# awm661tx_minimal.net
KiCad netlist of a schematic drawn in EAGLE
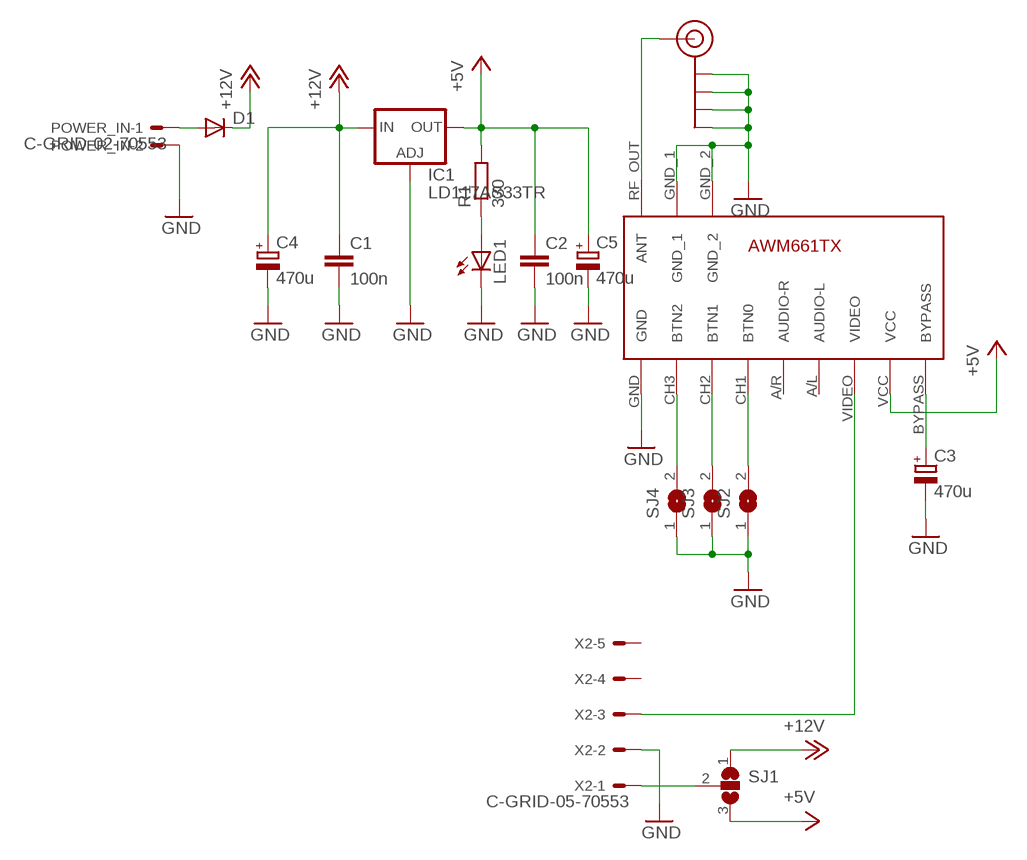
[diagram p0: schematic, sheet 1]

(export (version "E")
  (design (tool "Eeschema 10.0.6"))
  (components
    (comp (ref "C1")
      (value "100n")
      (footprint "eagle-import:C0805")
      (libsource (lib "eagle-import") (part "C-EUC0805"))
    )
    (comp (ref "C2")
      (value "100n")
      (footprint "eagle-import:C0805")
      (libsource (lib "eagle-import") (part "C-EUC0805"))
    )
    (comp (ref "C3")
      (value "470u")
      (footprint "eagle-import:150CLZ-0810")
      (libsource (lib "eagle-import") (part "CPOL-EU150CLZ-0810"))
    )
    (comp (ref "C4")
      (value "470u")
      (footprint "eagle-import:150CLZ-0810")
      (libsource (lib "eagle-import") (part "CPOL-EU150CLZ-0810"))
    )
    (comp (ref "C5")
      (value "470u")
      (footprint "eagle-import:150CLZ-0810")
      (libsource (lib "eagle-import") (part "CPOL-EU150CLZ-0810"))
    )
    (comp (ref "D1")
      (value "DIODE-MELF-MLL41")
      (footprint "eagle-import:MELF-MLL41")
      (libsource (lib "eagle-import") (part "DIODE-MELF-MLL41"))
    )
    (comp (ref "IC1")
      (value "LD117AS33TR")
      (footprint "eagle-import:SOT223")
      (libsource (lib "eagle-import") (part "LD117A?S33TR"))
    )
    (comp (ref "J$1")
      (value "SMA_EDGE")
      (footprint "eagle-import:SMA-EDGE")
      (libsource (lib "eagle-import") (part "SMA_EDGE"))
    )
    (comp (ref "LED1")
      (value "LEDCHIP-LED0805")
      (footprint "eagle-import:CHIP-LED0805")
      (libsource (lib "eagle-import") (part "LEDCHIP-LED0805"))
    )
    (comp (ref "POWER_IN")
      (value "C-GRID-02-70553")
      (footprint "eagle-import:70553-02")
      (libsource (lib "eagle-import") (part "C-GRID-02-70553"))
    )
    (comp (ref "R1")
      (value "330")
      (footprint "eagle-import:R0805")
      (libsource (lib "eagle-import") (part "R-EU_R0805"))
    )
    (comp (ref "SJ1")
      (value "SJ2W")
      (footprint "eagle-import:SJ_2")
      (libsource (lib "eagle-import") (part "SJ2W"))
    )
    (comp (ref "SJ2") (value "SJ") (footprint "eagle-import:SJ") (libsource (lib "eagle-import") (part "SJ")))
    (comp (ref "SJ3") (value "SJ") (footprint "eagle-import:SJ") (libsource (lib "eagle-import") (part "SJ")))
    (comp (ref "SJ4") (value "SJ") (footprint "eagle-import:SJ") (libsource (lib "eagle-import") (part "SJ")))
    (comp (ref "U$1")
      (value "AWM661TX")
      (footprint "eagle-import:AWM661TX")
      (libsource (lib "eagle-import") (part "AWM661TX"))
    )
    (comp (ref "X2")
      (value "C-GRID-05-70553")
      (footprint "eagle-import:70553-05")
      (libsource (lib "eagle-import") (part "C-GRID-05-70553"))
    )
  )
  (nets
    (net (code "1") (name "+5V") (class "Default")
      (node (ref "C2") (pin "1") (pinfunction "1_1") (pintype "passive"))
      (node (ref "C5") (pin "+") (pinfunction "+_+") (pintype "passive"))
      (node (ref "IC1") (pin "4") (pinfunction "OUT_4") (pintype "passive"))
      (node (ref "R1") (pin "2") (pinfunction "2_2") (pintype "passive"))
      (node (ref "SJ1") (pin "3") (pinfunction "3_3") (pintype "passive"))
      (node (ref "U$1") (pin "VCC") (pinfunction "VCC_VCC") (pintype "bidirectional"))
    )
    (net (code "2") (name "+12V") (class "Default")
      (node (ref "C1") (pin "1") (pinfunction "1_1") (pintype "passive"))
      (node (ref "C4") (pin "+") (pinfunction "+_+") (pintype "passive"))
      (node (ref "D1") (pin "C") (pinfunction "C_C") (pintype "passive"))
      (node (ref "IC1") (pin "3") (pinfunction "IN_3") (pintype "input"))
      (node (ref "SJ1") (pin "1") (pinfunction "1_1") (pintype "passive"))
    )
    (net (code "3") (name "GND") (class "Default")
      (node (ref "C1") (pin "2") (pinfunction "2_2") (pintype "passive"))
      (node (ref "C2") (pin "2") (pinfunction "2_2") (pintype "passive"))
      (node (ref "C3") (pin "-") (pinfunction "-_-") (pintype "passive"))
      (node (ref "C4") (pin "-") (pinfunction "-_-") (pintype "passive"))
      (node (ref "C5") (pin "-") (pinfunction "-_-") (pintype "passive"))
      (node (ref "IC1") (pin "1") (pinfunction "ADJ_1") (pintype "input"))
      (node (ref "J$1") (pin "GND@0") (pinfunction "GND_GND@0") (pintype "bidirectional"))
      (node (ref "J$1") (pin "GND@1") (pinfunction "GND_GND@1") (pintype "bidirectional"))
      (node (ref "J$1") (pin "GND@2") (pinfunction "GND_GND@2") (pintype "bidirectional"))
      (node (ref "J$1") (pin "GND@3") (pinfunction "GND_GND@3") (pintype "bidirectional"))
      (node (ref "LED1") (pin "C") (pinfunction "C_C") (pintype "passive"))
      (node (ref "POWER_IN") (pin "2") (pinfunction "S_2") (pintype "passive"))
      (node (ref "SJ2") (pin "1") (pinfunction "1_1") (pintype "passive"))
      (node (ref "SJ3") (pin "1") (pinfunction "1_1") (pintype "passive"))
      (node (ref "SJ4") (pin "1") (pinfunction "1_1") (pintype "passive"))
      (node (ref "U$1") (pin "GND") (pinfunction "GND_GND") (pintype "bidirectional"))
      (node (ref "U$1") (pin "GND_1") (pinfunction "GND_1_GND_1") (pintype "bidirectional"))
      (node (ref "U$1") (pin "GND_2") (pinfunction "GND_2_GND_2") (pintype "bidirectional"))
      (node (ref "X2") (pin "2") (pinfunction "S_2") (pintype "passive"))
    )
    (net (code "4") (name "Net-(C3-Pad+)") (class "Default")
      (node (ref "C3") (pin "+") (pinfunction "+_+") (pintype "passive"))
      (node (ref "U$1") (pin "BYPASS") (pinfunction "BYPASS_BYPASS") (pintype "bidirectional"))
    )
    (net (code "5") (name "Net-(J$1-SIGNAL)") (class "Default")
      (node (ref "J$1") (pin "SIG") (pinfunction "SIGNAL_SIG") (pintype "bidirectional"))
      (node (ref "U$1") (pin "RF_OUT") (pinfunction "ANT_RF_OUT") (pintype "bidirectional"))
    )
    (net (code "6") (name "Net-(LED1-PadA)") (class "Default")
      (node (ref "LED1") (pin "A") (pinfunction "A_A") (pintype "passive"))
      (node (ref "R1") (pin "1") (pinfunction "1_1") (pintype "passive"))
    )
    (net (code "7") (name "Net-(POWER_INA-S)") (class "Default")
      (node (ref "D1") (pin "A") (pinfunction "A_A") (pintype "passive"))
      (node (ref "POWER_IN") (pin "1") (pinfunction "S_1") (pintype "passive"))
    )
    (net (code "8") (name "Net-(U$1-BTN0)") (class "Default")
      (node (ref "SJ2") (pin "2") (pinfunction "2_2") (pintype "passive"))
      (node (ref "U$1") (pin "CH1") (pinfunction "BTN0_CH1") (pintype "bidirectional"))
    )
    (net (code "9") (name "Net-(U$1-BTN1)") (class "Default")
      (node (ref "SJ3") (pin "2") (pinfunction "2_2") (pintype "passive"))
      (node (ref "U$1") (pin "CH2") (pinfunction "BTN1_CH2") (pintype "bidirectional"))
    )
    (net (code "10") (name "Net-(U$1-BTN2)") (class "Default")
      (node (ref "SJ4") (pin "2") (pinfunction "2_2") (pintype "passive"))
      (node (ref "U$1") (pin "CH3") (pinfunction "BTN2_CH3") (pintype "bidirectional"))
    )
    (net (code "11") (name "Net-(X2A-S)") (class "Default")
      (node (ref "SJ1") (pin "2") (pinfunction "2_2") (pintype "passive"))
      (node (ref "X2") (pin "1") (pinfunction "S_1") (pintype "passive"))
    )
    (net (code "12") (name "Net-(X2C-S)") (class "Default")
      (node (ref "U$1") (pin "VIDEO") (pinfunction "VIDEO_VIDEO") (pintype "bidirectional"))
      (node (ref "X2") (pin "3") (pinfunction "S_3") (pintype "passive"))
    )
    (net (code "13") (name "unconnected-(U$1-AUDIO-L-PadA{slash}L)") (class "Default")
      (node (ref "U$1") (pin "A/L") (pinfunction "AUDIO-L_A/L") (pintype "bidirectional"))
    )
    (net (code "14") (name "unconnected-(U$1-AUDIO-R-PadA{slash}R)") (class "Default")
      (node (ref "U$1") (pin "A/R") (pinfunction "AUDIO-R_A/R") (pintype "bidirectional"))
    )
    (net (code "15") (name "unconnected-(X2D-S-Pad4)") (class "Default")
      (node (ref "X2") (pin "4") (pinfunction "S_4") (pintype "passive"))
    )
    (net (code "16") (name "unconnected-(X2E-S-Pad5)") (class "Default")
      (node (ref "X2") (pin "5") (pinfunction "S_5") (pintype "passive"))
    )
  )
)
